# Sheet2.net
KiCad netlist of a schematic drawn in Altium Designer
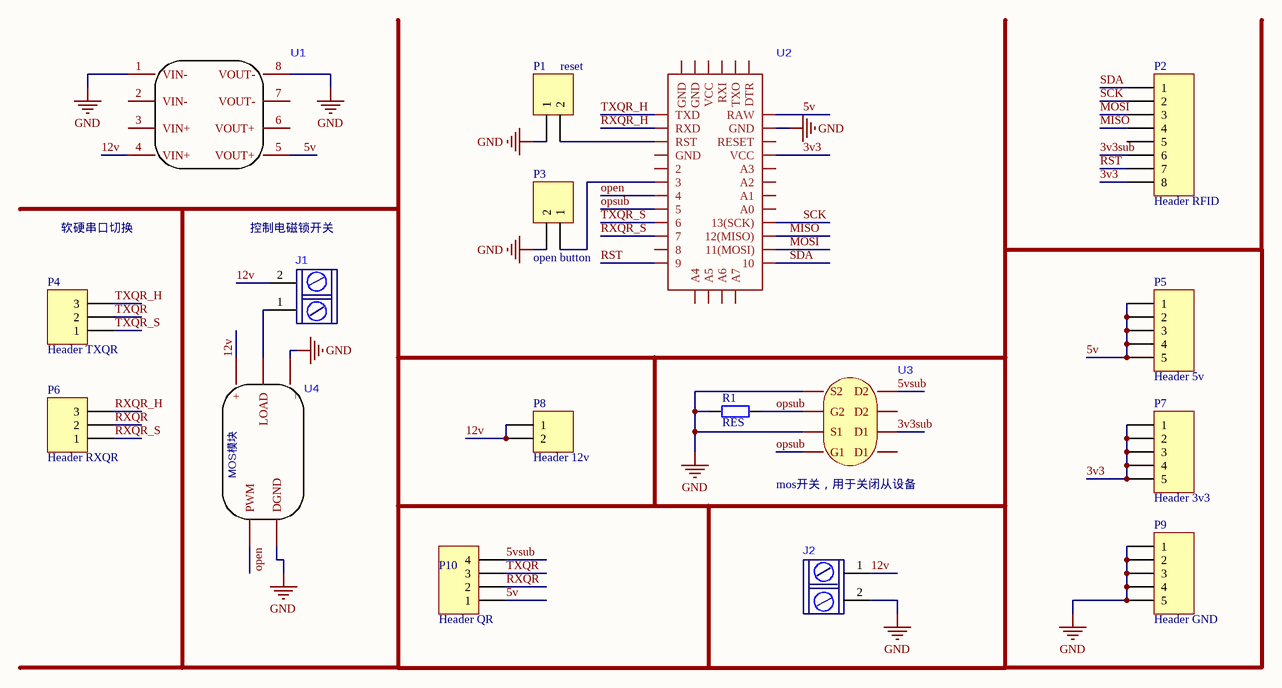
[diagram p0: Sheet2.SchDoc]

(export (version "E")
  (design (tool "Eeschema 10.0.6"))
  (components
    (comp (ref "J1")
      (value "~")
      (footprint "KF301-5.0-2P")
      (libsource (lib "altium-import") (part "root_0_KF301_"))
    )
    (comp (ref "J2")
      (value "~")
      (footprint "KF301-5.0-2P")
      (libsource (lib "altium-import") (part "root_2_KF301_"))
    )
    (comp (ref "P1")
      (value "reset")
      (footprint "HDR1X2")
      (description "Header, 2-Pin")
      (fields (field (name "PUBLISHER") "Altium Limited"))
      (libsource (lib "") (part "Header 2_1"))
    )
    (comp (ref "P2")
      (value "Header RFID")
      (footprint "HDR1X8")
      (description "Header, 8-Pin")
      (fields (field (name "PUBLISHER") "Altium Limited"))
      (libsource (lib "Miscellaneous Connectors") (part "Header 8"))
    )
    (comp (ref "P3")
      (value "open button")
      (footprint "HDR1X2")
      (description "Header, 2-Pin")
      (fields (field (name "PUBLISHER") "Altium Limited"))
      (libsource (lib "Miscellaneous Connectors") (part "Header 2"))
    )
    (comp (ref "P4")
      (value "Header TXQR")
      (footprint "HDR1X3")
      (description "Header, 3-Pin")
      (fields (field (name "PUBLISHER") "Altium Limited"))
      (libsource (lib "Miscellaneous Connectors") (part "Header 3"))
    )
    (comp (ref "P5")
      (value "Header 5v")
      (footprint "HDR1X5")
      (description "Header, 5-Pin")
      (fields (field (name "PUBLISHER") "Altium Limited"))
      (libsource (lib "Miscellaneous Connectors") (part "Header 5"))
    )
    (comp (ref "P6")
      (value "Header RXQR")
      (footprint "HDR1X3")
      (description "Header, 3-Pin")
      (fields (field (name "PUBLISHER") "Altium Limited"))
      (libsource (lib "Miscellaneous Connectors") (part "Header 3"))
    )
    (comp (ref "P7")
      (value "Header 3v3")
      (footprint "HDR1X5")
      (description "Header, 5-Pin")
      (fields (field (name "PUBLISHER") "Altium Limited"))
      (libsource (lib "Miscellaneous Connectors") (part "Header 5"))
    )
    (comp (ref "P8")
      (value "Header 12v")
      (footprint "HDR1X2")
      (description "Header, 2-Pin")
      (fields (field (name "PUBLISHER") "Altium Limited"))
      (libsource (lib "Miscellaneous Connectors") (part "Header 2"))
    )
    (comp (ref "P9")
      (value "Header GND")
      (footprint "HDR1X5")
      (description "Header, 5-Pin")
      (fields (field (name "PUBLISHER") "Altium Limited"))
      (libsource (lib "Miscellaneous Connectors") (part "Header 5"))
    )
    (comp (ref "P10")
      (value "Header QR")
      (footprint "HDR1X4")
      (description "Header, 4-Pin")
      (fields (field (name "PUBLISHER") "Altium Limited"))
      (libsource (lib "Miscellaneous Connectors") (part "Header 4"))
    )
    (comp (ref "R1")
      (value "RES")
      (footprint "General:0603")
      (description "Resistor")
      (libsource (lib "General") (part "RES"))
    )
    (comp (ref "U1")
      (value "~")
      (footprint "MP1584EN_3A")
      (libsource (lib "altium-import") (part "root_0_MP1584EN_3A_"))
    )
    (comp (ref "U2")
      (value "~")
      (footprint "ARDUINO-LGT8F-328D_AS_PRO_MINI-PRO-2")
      (libsource (lib "altium-import") (part "root_0_ARDUINO-PRO-MINI_"))
    )
    (comp (ref "U3")
      (value "~")
      (footprint "IC-MOS-9926A-SOP8")
      (libsource (lib "altium-import") (part "root_0_IC-9926A_"))
    )
    (comp (ref "U4")
      (value "~")
      (footprint "PCBComponent_1 - duplicate")
      (libsource (lib "altium-import") (part "root_1_光耦隔离MOSFET模块_"))
    )
  )
  (nets
    (net (code "1") (name "/3v3") (class "Default")
      (node (ref "P2") (pin "8") (pinfunction "8_8") (pintype "passive"))
      (node (ref "P7") (pin "1") (pinfunction "1_1") (pintype "passive"))
      (node (ref "P7") (pin "2") (pinfunction "2_2") (pintype "passive"))
      (node (ref "P7") (pin "3") (pinfunction "3_3") (pintype "passive"))
      (node (ref "P7") (pin "4") (pinfunction "4_4") (pintype "passive"))
      (node (ref "P7") (pin "5") (pinfunction "5_5") (pintype "passive"))
      (node (ref "U2") (pin "21") (pinfunction "VCC_21") (pintype "passive"))
    )
    (net (code "2") (name "/3v3sub") (class "Default")
      (node (ref "P2") (pin "6") (pinfunction "6_6") (pintype "passive"))
      (node (ref "U3") (pin "D1") (pinfunction "D1_D1") (pintype "passive"))
    )
    (net (code "3") (name "/5v") (class "Default")
      (node (ref "P10") (pin "1") (pinfunction "1_1") (pintype "passive"))
      (node (ref "P5") (pin "1") (pinfunction "1_1") (pintype "passive"))
      (node (ref "P5") (pin "2") (pinfunction "2_2") (pintype "passive"))
      (node (ref "P5") (pin "3") (pinfunction "3_3") (pintype "passive"))
      (node (ref "P5") (pin "4") (pinfunction "4_4") (pintype "passive"))
      (node (ref "P5") (pin "5") (pinfunction "5_5") (pintype "passive"))
      (node (ref "U1") (pin "5") (pinfunction "VOUT+_5") (pintype "passive"))
      (node (ref "U2") (pin "24") (pinfunction "RAW_24") (pintype "passive"))
    )
    (net (code "4") (name "/5vsub") (class "Default")
      (node (ref "P10") (pin "4") (pinfunction "4_4") (pintype "passive"))
      (node (ref "U3") (pin "D2") (pinfunction "D2_D2") (pintype "passive"))
    )
    (net (code "5") (name "/12v") (class "Default")
      (node (ref "J1") (pin "2") (pinfunction "1_2") (pintype "passive"))
      (node (ref "J2") (pin "1") (pinfunction "1_1") (pintype "passive"))
      (node (ref "P8") (pin "1") (pinfunction "1_1") (pintype "passive"))
      (node (ref "P8") (pin "2") (pinfunction "2_2") (pintype "passive"))
      (node (ref "U1") (pin "4") (pinfunction "VIN+_4") (pintype "passive"))
      (node (ref "U4") (pin "3") (pinfunction "+_3") (pintype "passive"))
    )
    (net (code "6") (name "/MISO") (class "Default")
      (node (ref "P2") (pin "4") (pinfunction "4_4") (pintype "passive"))
      (node (ref "U2") (pin "15") (pinfunction "12(MISO)_15") (pintype "passive"))
    )
    (net (code "7") (name "/MOSI") (class "Default")
      (node (ref "P2") (pin "3") (pinfunction "3_3") (pintype "passive"))
      (node (ref "U2") (pin "14") (pinfunction "11(MOSI)_14") (pintype "passive"))
    )
    (net (code "8") (name "/RST") (class "Default")
      (node (ref "P2") (pin "7") (pinfunction "7_7") (pintype "passive"))
      (node (ref "U2") (pin "12") (pinfunction "9_12") (pintype "passive"))
    )
    (net (code "9") (name "/RXQR") (class "Default")
      (node (ref "P10") (pin "2") (pinfunction "2_2") (pintype "passive"))
      (node (ref "P6") (pin "2") (pinfunction "2_2") (pintype "passive"))
    )
    (net (code "10") (name "/RXQR_H") (class "Default")
      (node (ref "P6") (pin "3") (pinfunction "3_3") (pintype "passive"))
      (node (ref "U2") (pin "2") (pinfunction "RXD_2") (pintype "passive"))
    )
    (net (code "11") (name "/RXQR_S") (class "Default")
      (node (ref "P6") (pin "1") (pinfunction "1_1") (pintype "passive"))
      (node (ref "U2") (pin "10") (pinfunction "7_10") (pintype "passive"))
    )
    (net (code "12") (name "/SCK") (class "Default")
      (node (ref "P2") (pin "2") (pinfunction "2_2") (pintype "passive"))
      (node (ref "U2") (pin "16") (pinfunction "13(SCK)_16") (pintype "passive"))
    )
    (net (code "13") (name "/SDA") (class "Default")
      (node (ref "P2") (pin "1") (pinfunction "1_1") (pintype "passive"))
      (node (ref "U2") (pin "13") (pinfunction "10_13") (pintype "passive"))
    )
    (net (code "14") (name "/TXQR") (class "Default")
      (node (ref "P10") (pin "3") (pinfunction "3_3") (pintype "passive"))
      (node (ref "P4") (pin "2") (pinfunction "2_2") (pintype "passive"))
    )
    (net (code "15") (name "/TXQR_H") (class "Default")
      (node (ref "P4") (pin "3") (pinfunction "3_3") (pintype "passive"))
      (node (ref "U2") (pin "1") (pinfunction "TXD_1") (pintype "passive"))
    )
    (net (code "16") (name "/TXQR_S") (class "Default")
      (node (ref "P4") (pin "1") (pinfunction "1_1") (pintype "passive"))
      (node (ref "U2") (pin "9") (pinfunction "6_9") (pintype "passive"))
    )
    (net (code "17") (name "/open") (class "Default")
      (node (ref "U2") (pin "7") (pinfunction "4_7") (pintype "passive"))
      (node (ref "U4") (pin "1") (pinfunction "PWM_1") (pintype "passive"))
    )
    (net (code "18") (name "/opsub") (class "Default")
      (node (ref "R1") (pin "2") (pinfunction "2_2") (pintype "passive"))
      (node (ref "U2") (pin "8") (pinfunction "5_8") (pintype "passive"))
      (node (ref "U3") (pin "G1") (pinfunction "G1_G1") (pintype "passive"))
      (node (ref "U3") (pin "G2") (pinfunction "G2_G2") (pintype "passive"))
    )
    (net (code "19") (name "GND") (class "Default")
      (node (ref "J2") (pin "2") (pinfunction "1_2") (pintype "passive"))
      (node (ref "P1") (pin "1") (pinfunction "1_1") (pintype "passive"))
      (node (ref "P3") (pin "2") (pinfunction "2_2") (pintype "passive"))
      (node (ref "P9") (pin "1") (pinfunction "1_1") (pintype "passive"))
      (node (ref "P9") (pin "2") (pinfunction "2_2") (pintype "passive"))
      (node (ref "P9") (pin "3") (pinfunction "3_3") (pintype "passive"))
      (node (ref "P9") (pin "4") (pinfunction "4_4") (pintype "passive"))
      (node (ref "P9") (pin "5") (pinfunction "5_5") (pintype "passive"))
      (node (ref "R1") (pin "1") (pinfunction "1_1") (pintype "passive"))
      (node (ref "U1") (pin "1") (pinfunction "VIN-_1") (pintype "passive"))
      (node (ref "U1") (pin "8") (pinfunction "VOUT-_8") (pintype "passive"))
      (node (ref "U2") (pin "23") (pinfunction "GND_23") (pintype "passive"))
      (node (ref "U3") (pin "S1") (pinfunction "S1_S1") (pintype "passive"))
      (node (ref "U3") (pin "S2") (pinfunction "S2_S2") (pintype "passive"))
      (node (ref "U4") (pin "2") (pinfunction "DGND_2") (pintype "passive"))
      (node (ref "U4") (pin "5") (pinfunction "__5") (pintype "passive"))
    )
    (net (code "20") (name "Net-(U2-3)") (class "Default")
      (node (ref "P3") (pin "1") (pinfunction "1_1") (pintype "passive"))
      (node (ref "U2") (pin "6") (pinfunction "3_6") (pintype "passive"))
    )
    (net (code "21") (name "Net-(U2-RST)") (class "Default")
      (node (ref "P1") (pin "2") (pinfunction "2_2") (pintype "passive"))
      (node (ref "U2") (pin "3") (pinfunction "RST_3") (pintype "passive"))
    )
    (net (code "22") (name "Net-(U4-LOAD)") (class "Default")
      (node (ref "J1") (pin "1") (pinfunction "1_1") (pintype "passive"))
      (node (ref "U4") (pin "4") (pinfunction "LOAD_4") (pintype "passive"))
    )
    (net (code "23") (name "unconnected-(P2-Pad5)") (class "Default")
      (node (ref "P2") (pin "5") (pinfunction "5_5") (pintype "passive"))
    )
    (net (code "24") (name "unconnected-(U1-VIN+-Pad3)") (class "Default")
      (node (ref "U1") (pin "3") (pinfunction "VIN+_3") (pintype "passive"))
    )
    (net (code "25") (name "unconnected-(U1-VIN--Pad2)") (class "Default")
      (node (ref "U1") (pin "2") (pinfunction "VIN-_2") (pintype "passive"))
    )
    (net (code "26") (name "unconnected-(U1-VOUT+-Pad6)") (class "Default")
      (node (ref "U1") (pin "6") (pinfunction "VOUT+_6") (pintype "passive"))
    )
    (net (code "27") (name "unconnected-(U1-VOUT--Pad7)") (class "Default")
      (node (ref "U1") (pin "7") (pinfunction "VOUT-_7") (pintype "passive"))
    )
    (net (code "28") (name "unconnected-(U2-2-Pad5)") (class "Default")
      (node (ref "U2") (pin "5") (pinfunction "2_5") (pintype "passive"))
    )
    (net (code "29") (name "unconnected-(U2-8-Pad11)") (class "Default")
      (node (ref "U2") (pin "11") (pinfunction "8_11") (pintype "passive"))
    )
    (net (code "30") (name "unconnected-(U2-A0-Pad17)") (class "Default")
      (node (ref "U2") (pin "17") (pinfunction "A0_17") (pintype "passive"))
    )
    (net (code "31") (name "unconnected-(U2-A1-Pad18)") (class "Default")
      (node (ref "U2") (pin "18") (pinfunction "A1_18") (pintype "passive"))
    )
    (net (code "32") (name "unconnected-(U2-A2-Pad19)") (class "Default")
      (node (ref "U2") (pin "19") (pinfunction "A2_19") (pintype "passive"))
    )
    (net (code "33") (name "unconnected-(U2-A3-Pad20)") (class "Default")
      (node (ref "U2") (pin "20") (pinfunction "A3_20") (pintype "passive"))
    )
    (net (code "34") (name "unconnected-(U2-A4-Pad31)") (class "Default")
      (node (ref "U2") (pin "31") (pinfunction "A4_31") (pintype "passive"))
    )
    (net (code "35") (name "unconnected-(U2-A5-Pad32)") (class "Default")
      (node (ref "U2") (pin "32") (pinfunction "A5_32") (pintype "passive"))
    )
    (net (code "36") (name "unconnected-(U2-A6-Pad33)") (class "Default")
      (node (ref "U2") (pin "33") (pinfunction "A6_33") (pintype "passive"))
    )
    (net (code "37") (name "unconnected-(U2-A7-Pad34)") (class "Default")
      (node (ref "U2") (pin "34") (pinfunction "A7_34") (pintype "passive"))
    )
    (net (code "38") (name "unconnected-(U2-DTR-Pad25)") (class "Default")
      (node (ref "U2") (pin "25") (pinfunction "DTR_25") (pintype "passive"))
    )
    (net (code "39") (name "unconnected-(U2-GND-Pad4)") (class "Default")
      (node (ref "U2") (pin "4") (pinfunction "GND_4") (pintype "passive"))
    )
    (net (code "40") (name "unconnected-(U2-GND-Pad29)") (class "Default")
      (node (ref "U2") (pin "29") (pinfunction "GND_29") (pintype "passive"))
    )
    (net (code "41") (name "unconnected-(U2-GND-Pad30)") (class "Default")
      (node (ref "U2") (pin "30") (pinfunction "GND_30") (pintype "passive"))
    )
    (net (code "42") (name "unconnected-(U2-RESET-Pad22)") (class "Default")
      (node (ref "U2") (pin "22") (pinfunction "RESET_22") (pintype "passive"))
    )
    (net (code "43") (name "unconnected-(U2-RXI-Pad27)") (class "Default")
      (node (ref "U2") (pin "27") (pinfunction "RXI_27") (pintype "passive"))
    )
    (net (code "44") (name "unconnected-(U2-TXO-Pad26)") (class "Default")
      (node (ref "U2") (pin "26") (pinfunction "TXO_26") (pintype "passive"))
    )
    (net (code "45") (name "unconnected-(U2-VCC-Pad28)") (class "Default")
      (node (ref "U2") (pin "28") (pinfunction "VCC_28") (pintype "passive"))
    )
    (net (code "46") (name "unconnected-(U3-PadD1)") (class "Default")
      (node (ref "U3") (pin "D1") (pinfunction "D1_D1") (pintype "passive"))
    )
    (net (code "47") (name "unconnected-(U3-PadD2)") (class "Default")
      (node (ref "U3") (pin "D2") (pinfunction "D2_D2") (pintype "passive"))
    )
  )
)
